# schematic.net
KiCad netlist of a schematic drawn in EAGLE
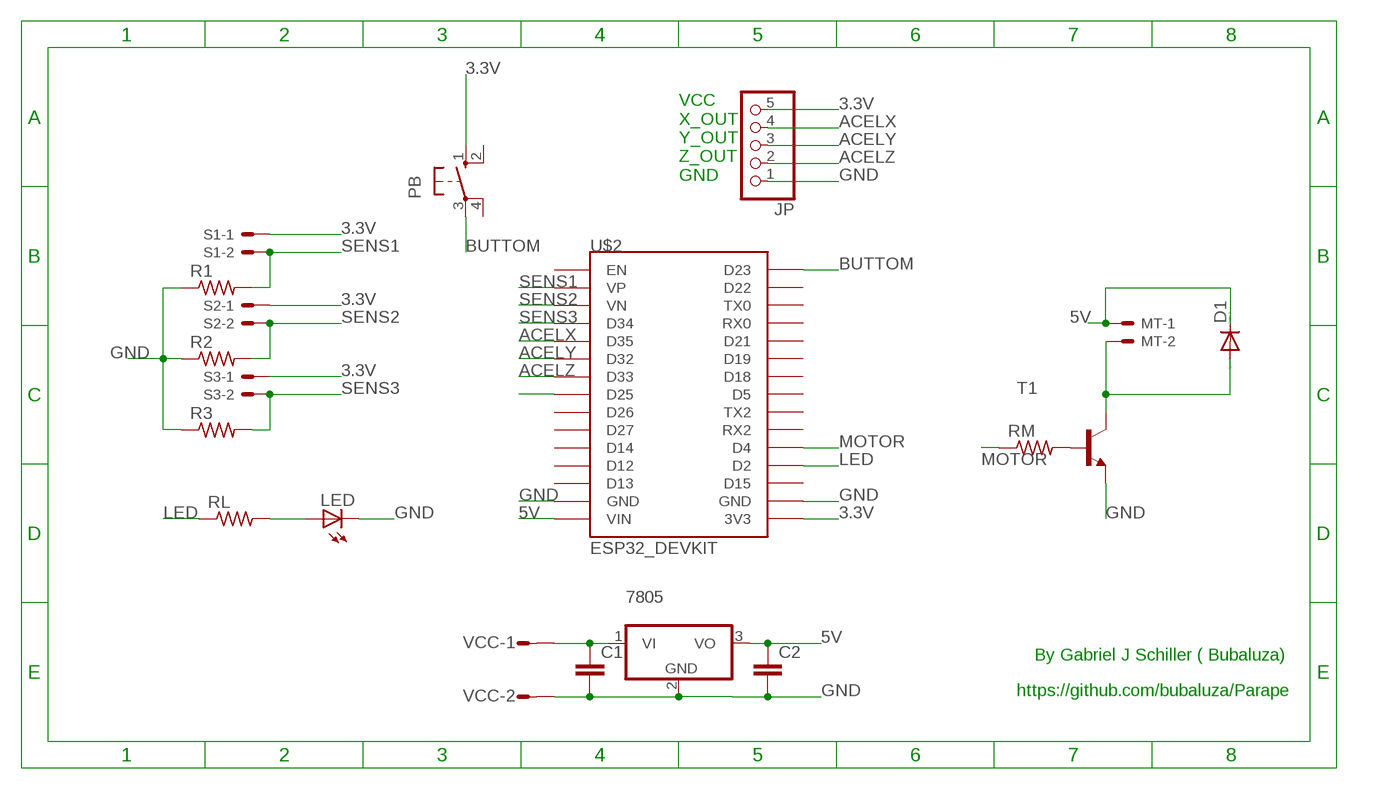
[diagram p0: schematic, sheet 1]

(export (version "E")
  (design (tool "Eeschema 10.0.6"))
  (components
    (comp (ref "7805")
      (value "786TV")
      (footprint "eagle-import:TO220V")
      (libsource (lib "eagle-import") (part "78TV6"))
    )
    (comp (ref "C1")
      (value "C2,5-3")
      (footprint "eagle-import:C2.5-3")
      (libsource (lib "eagle-import") (part "C2,5-3"))
    )
    (comp (ref "C2")
      (value "C2,5-3")
      (footprint "eagle-import:C2.5-3")
      (libsource (lib "eagle-import") (part "C2,5-3"))
    )
    (comp (ref "D1")
      (value "1N4148DO35-10")
      (footprint "eagle-import:DO35-10")
      (libsource (lib "eagle-import") (part "1N4148DO35-10"))
    )
    (comp (ref "JP")
      (value "PINHD-1X5")
      (footprint "eagle-import:1X05")
      (libsource (lib "eagle-import") (part "PINHD-1X5"))
    )
    (comp (ref "LED")
      (value "LED5MM")
      (footprint "eagle-import:LED5MM")
      (libsource (lib "eagle-import") (part "LED5MM"))
    )
    (comp (ref "MT")
      (value "332-02")
      (footprint "eagle-import:332-02")
      (libsource (lib "eagle-import") (part "332-02"))
    )
    (comp (ref "PB")
      (value "10-XX")
      (footprint "eagle-import:B3F-10XX")
      (fields (field (name "MPN") "B3F-1000"))
      (libsource (lib "eagle-import") (part "10-XX"))
    )
    (comp (ref "R1")
      (value "R-US_0207/7")
      (footprint "eagle-import:0207_7")
      (libsource (lib "eagle-import") (part "R-US_0207/7"))
    )
    (comp (ref "R2")
      (value "R-US_0207/7")
      (footprint "eagle-import:0207_7")
      (libsource (lib "eagle-import") (part "R-US_0207/7"))
    )
    (comp (ref "R3")
      (value "R-US_0207/7")
      (footprint "eagle-import:0207_7")
      (libsource (lib "eagle-import") (part "R-US_0207/7"))
    )
    (comp (ref "RL")
      (value "R-US_0207/7")
      (footprint "eagle-import:0207_7")
      (libsource (lib "eagle-import") (part "R-US_0207/7"))
    )
    (comp (ref "RM")
      (value "R-US_0207/7")
      (footprint "eagle-import:0207_7")
      (libsource (lib "eagle-import") (part "R-US_0207/7"))
    )
    (comp (ref "S1")
      (value "332-02")
      (footprint "eagle-import:332-02")
      (libsource (lib "eagle-import") (part "332-02"))
    )
    (comp (ref "S2")
      (value "332-02")
      (footprint "eagle-import:332-02")
      (libsource (lib "eagle-import") (part "332-02"))
    )
    (comp (ref "S3")
      (value "332-02")
      (footprint "eagle-import:332-02")
      (libsource (lib "eagle-import") (part "332-02"))
    )
    (comp (ref "T1")
      (value "2N2222")
      (footprint "eagle-import:TO18")
      (libsource (lib "eagle-import") (part "2N2222"))
    )
    (comp (ref "U$2")
      (value "ESP32_DEVKIT")
      (footprint "eagle-import:ESP32_DEVKIT")
      (libsource (lib "eagle-import") (part "ESP32_DEVKIT"))
    )
    (comp (ref "VCC")
      (value "L02P")
      (footprint "eagle-import:L02P")
      (libsource (lib "eagle-import") (part "L02P"))
    )
  )
  (nets
    (net (code "1") (name "/3.3V") (class "Default")
      (node (ref "JP") (pin "5") (pinfunction "5_5") (pintype "passive"))
      (node (ref "PB") (pin "1") (pinfunction "S_1") (pintype "passive"))
      (node (ref "S1") (pin "1") (pinfunction "S_1") (pintype "passive"))
      (node (ref "S2") (pin "1") (pinfunction "S_1") (pintype "passive"))
      (node (ref "S3") (pin "1") (pinfunction "S_1") (pintype "passive"))
      (node (ref "U$2") (pin "3V3") (pinfunction "3V3_3V3") (pintype "bidirectional"))
    )
    (net (code "2") (name "/5V") (class "Default")
      (node (ref "7805") (pin "3") (pinfunction "VO_3") (pintype "passive"))
      (node (ref "C2") (pin "1") (pinfunction "1_1") (pintype "passive"))
      (node (ref "D1") (pin "C") (pinfunction "C_C") (pintype "passive"))
      (node (ref "MT") (pin "1") (pinfunction "S_1") (pintype "passive"))
      (node (ref "U$2") (pin "VIN") (pinfunction "VIN_VIN") (pintype "bidirectional"))
    )
    (net (code "3") (name "/ACELX") (class "Default")
      (node (ref "JP") (pin "4") (pinfunction "4_4") (pintype "passive"))
      (node (ref "U$2") (pin "D35") (pinfunction "D35_D35") (pintype "bidirectional"))
    )
    (net (code "4") (name "/ACELY") (class "Default")
      (node (ref "JP") (pin "3") (pinfunction "3_3") (pintype "passive"))
      (node (ref "U$2") (pin "D32") (pinfunction "D32_D32") (pintype "bidirectional"))
    )
    (net (code "5") (name "/ACELZ") (class "Default")
      (node (ref "JP") (pin "2") (pinfunction "2_2") (pintype "passive"))
      (node (ref "U$2") (pin "D33") (pinfunction "D33_D33") (pintype "bidirectional"))
    )
    (net (code "6") (name "/BUTTOM") (class "Default")
      (node (ref "PB") (pin "3") (pinfunction "P_3") (pintype "passive"))
      (node (ref "U$2") (pin "D23") (pinfunction "D23_D23") (pintype "bidirectional"))
    )
    (net (code "7") (name "/GND") (class "Default")
      (node (ref "7805") (pin "2") (pinfunction "GND_2") (pintype "passive"))
      (node (ref "C1") (pin "2") (pinfunction "2_2") (pintype "passive"))
      (node (ref "C2") (pin "2") (pinfunction "2_2") (pintype "passive"))
      (node (ref "JP") (pin "1") (pinfunction "1_1") (pintype "passive"))
      (node (ref "LED") (pin "K") (pinfunction "C_K") (pintype "passive"))
      (node (ref "R1") (pin "1") (pinfunction "1_1") (pintype "passive"))
      (node (ref "R2") (pin "1") (pinfunction "1_1") (pintype "passive"))
      (node (ref "R3") (pin "1") (pinfunction "1_1") (pintype "passive"))
      (node (ref "T1") (pin "1") (pinfunction "E_1") (pintype "passive"))
      (node (ref "U$2") (pin "GND@1") (pinfunction "GND_GND@1") (pintype "bidirectional"))
      (node (ref "U$2") (pin "GND@2") (pinfunction "GND_GND@2") (pintype "bidirectional"))
      (node (ref "VCC") (pin "2") (pinfunction "S_2") (pintype "passive"))
    )
    (net (code "8") (name "/LED") (class "Default")
      (node (ref "RL") (pin "1") (pinfunction "1_1") (pintype "passive"))
      (node (ref "U$2") (pin "D2") (pinfunction "D2_D2") (pintype "bidirectional"))
    )
    (net (code "9") (name "/MOTOR") (class "Default")
      (node (ref "RM") (pin "1") (pinfunction "1_1") (pintype "passive"))
      (node (ref "U$2") (pin "D4") (pinfunction "D4_D4") (pintype "bidirectional"))
    )
    (net (code "10") (name "/SENS1") (class "Default")
      (node (ref "R1") (pin "2") (pinfunction "2_2") (pintype "passive"))
      (node (ref "S1") (pin "2") (pinfunction "S_2") (pintype "passive"))
      (node (ref "U$2") (pin "VP") (pinfunction "VP_VP") (pintype "bidirectional"))
    )
    (net (code "11") (name "/SENS2") (class "Default")
      (node (ref "R2") (pin "2") (pinfunction "2_2") (pintype "passive"))
      (node (ref "S2") (pin "2") (pinfunction "S_2") (pintype "passive"))
      (node (ref "U$2") (pin "VN") (pinfunction "VN_VN") (pintype "bidirectional"))
    )
    (net (code "12") (name "/SENS3") (class "Default")
      (node (ref "R3") (pin "2") (pinfunction "2_2") (pintype "passive"))
      (node (ref "S3") (pin "2") (pinfunction "S_2") (pintype "passive"))
      (node (ref "U$2") (pin "D34") (pinfunction "D34_D34") (pintype "bidirectional"))
    )
    (net (code "13") (name "Net-(7805-VI)") (class "Default")
      (node (ref "7805") (pin "1") (pinfunction "VI_1") (pintype "input"))
      (node (ref "C1") (pin "1") (pinfunction "1_1") (pintype "passive"))
      (node (ref "VCC") (pin "1") (pinfunction "S_1") (pintype "passive"))
    )
    (net (code "14") (name "Net-(LED-PadA)") (class "Default")
      (node (ref "LED") (pin "A") (pinfunction "A_A") (pintype "passive"))
      (node (ref "RL") (pin "2") (pinfunction "2_2") (pintype "passive"))
    )
    (net (code "15") (name "Net-(MTB-S)") (class "Default")
      (node (ref "D1") (pin "A") (pinfunction "A_A") (pintype "passive"))
      (node (ref "MT") (pin "2") (pinfunction "S_2") (pintype "passive"))
      (node (ref "T1") (pin "3") (pinfunction "C_3") (pintype "passive"))
    )
    (net (code "16") (name "Net-(T1-B)") (class "Default")
      (node (ref "RM") (pin "2") (pinfunction "2_2") (pintype "passive"))
      (node (ref "T1") (pin "2") (pinfunction "B_2") (pintype "passive"))
    )
    (net (code "17") (name "unconnected-(PB-P1-Pad4)") (class "Default")
      (node (ref "PB") (pin "4") (pinfunction "P1_4") (pintype "passive"))
    )
    (net (code "18") (name "unconnected-(PB-S1-Pad2)") (class "Default")
      (node (ref "PB") (pin "2") (pinfunction "S1_2") (pintype "passive"))
    )
    (net (code "19") (name "unconnected-(U$2-PadD5)") (class "Default")
      (node (ref "U$2") (pin "D5") (pinfunction "D5_D5") (pintype "bidirectional"))
    )
    (net (code "20") (name "unconnected-(U$2-PadD12)") (class "Default")
      (node (ref "U$2") (pin "D12") (pinfunction "D12_D12") (pintype "bidirectional"))
    )
    (net (code "21") (name "unconnected-(U$2-PadD13)") (class "Default")
      (node (ref "U$2") (pin "D13") (pinfunction "D13_D13") (pintype "bidirectional"))
    )
    (net (code "22") (name "unconnected-(U$2-PadD14)") (class "Default")
      (node (ref "U$2") (pin "D14") (pinfunction "D14_D14") (pintype "bidirectional"))
    )
    (net (code "23") (name "unconnected-(U$2-PadD15)") (class "Default")
      (node (ref "U$2") (pin "D15") (pinfunction "D15_D15") (pintype "bidirectional"))
    )
    (net (code "24") (name "unconnected-(U$2-PadD18)") (class "Default")
      (node (ref "U$2") (pin "D18") (pinfunction "D18_D18") (pintype "bidirectional"))
    )
    (net (code "25") (name "unconnected-(U$2-PadD19)") (class "Default")
      (node (ref "U$2") (pin "D19") (pinfunction "D19_D19") (pintype "bidirectional"))
    )
    (net (code "26") (name "unconnected-(U$2-PadD21)") (class "Default")
      (node (ref "U$2") (pin "D21") (pinfunction "D21_D21") (pintype "bidirectional"))
    )
    (net (code "27") (name "unconnected-(U$2-PadD22)") (class "Default")
      (node (ref "U$2") (pin "D22") (pinfunction "D22_D22") (pintype "bidirectional"))
    )
    (net (code "28") (name "unconnected-(U$2-PadD25)") (class "Default")
      (node (ref "U$2") (pin "D25") (pinfunction "D25_D25") (pintype "bidirectional"))
    )
    (net (code "29") (name "unconnected-(U$2-PadD26)") (class "Default")
      (node (ref "U$2") (pin "D26") (pinfunction "D26_D26") (pintype "bidirectional"))
    )
    (net (code "30") (name "unconnected-(U$2-PadD27)") (class "Default")
      (node (ref "U$2") (pin "D27") (pinfunction "D27_D27") (pintype "bidirectional"))
    )
    (net (code "31") (name "unconnected-(U$2-PadEN)") (class "Default")
      (node (ref "U$2") (pin "EN") (pinfunction "EN_EN") (pintype "bidirectional"))
    )
    (net (code "32") (name "unconnected-(U$2-PadRX0)") (class "Default")
      (node (ref "U$2") (pin "RX0") (pinfunction "RX0_RX0") (pintype "bidirectional"))
    )
    (net (code "33") (name "unconnected-(U$2-PadRX2)") (class "Default")
      (node (ref "U$2") (pin "RX2") (pinfunction "RX2_RX2") (pintype "bidirectional"))
    )
    (net (code "34") (name "unconnected-(U$2-PadTX0)") (class "Default")
      (node (ref "U$2") (pin "TX0") (pinfunction "TX0_TX0") (pintype "bidirectional"))
    )
    (net (code "35") (name "unconnected-(U$2-PadTX2)") (class "Default")
      (node (ref "U$2") (pin "TX2") (pinfunction "TX2_TX2") (pintype "bidirectional"))
    )
  )
)
